# relays3.net
KiCad netlist of a schematic drawn in Altium Designer
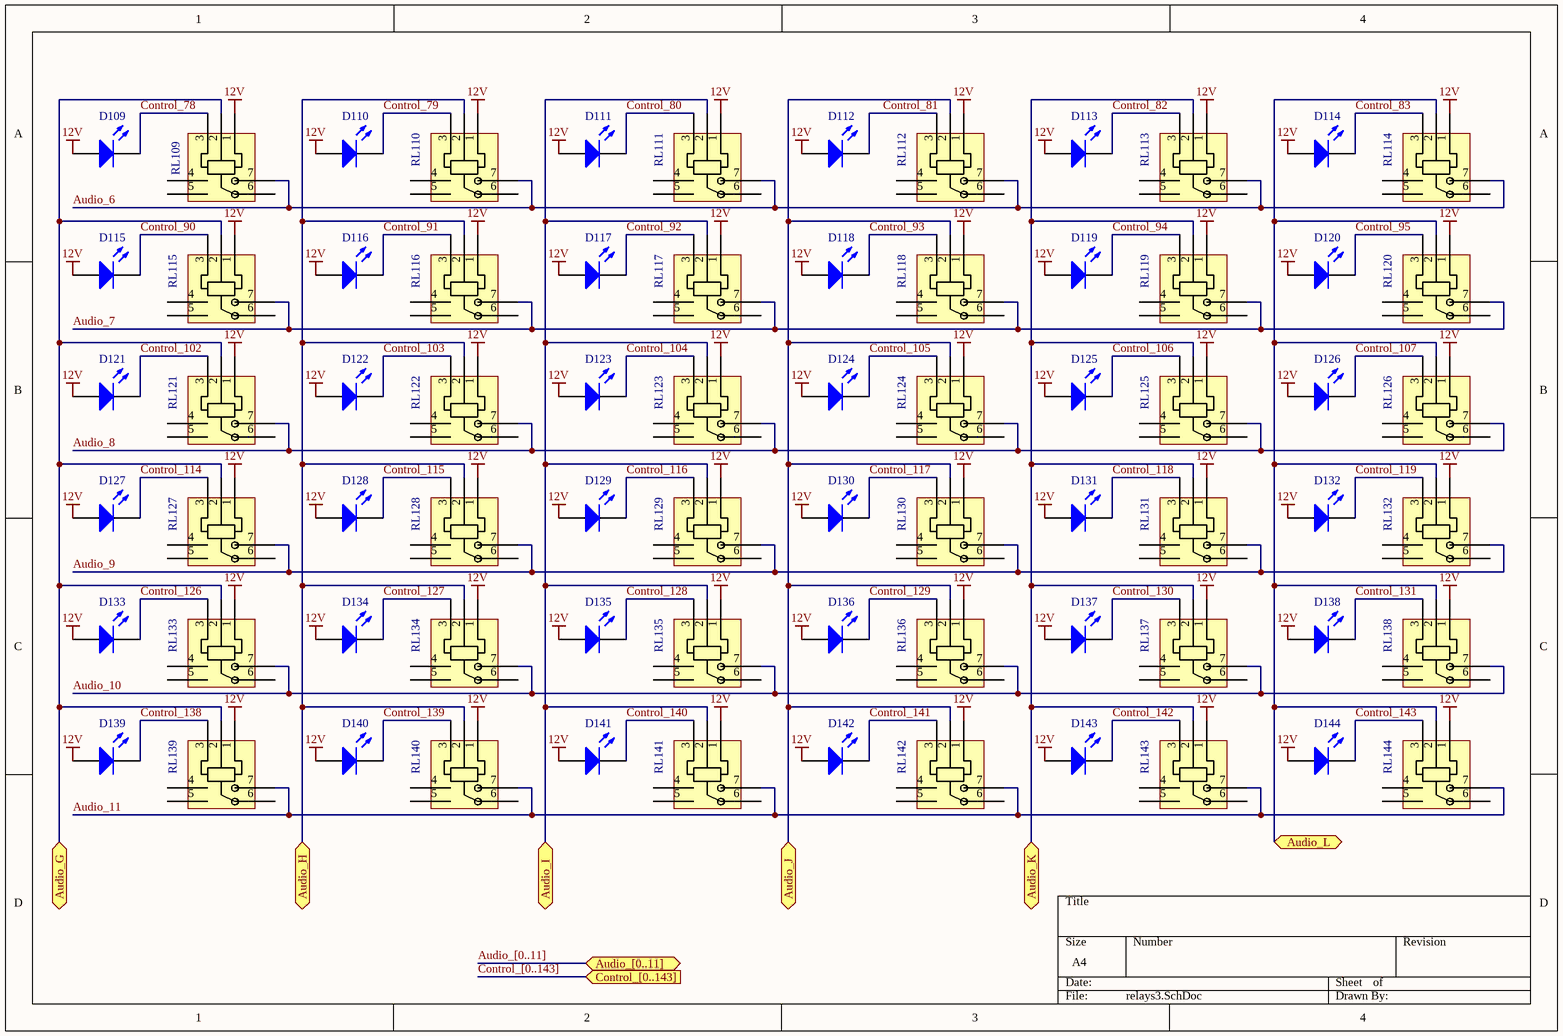
[diagram p0: relays3.SchDoc]

(export (version "E")
  (design (tool "Eeschema 10.0.6"))
  (components
    (comp (ref "D109")
      (value "LED0")
      (footprint "LED_round_5mm")
      (description "Typical INFRARED GaAs LED")
      (fields (field (name "PUBLISHER") "Altium Limited"))
      (libsource (lib "Miscellaneous Devices") (part "LED0"))
    )
    (comp (ref "D110")
      (value "LED0")
      (footprint "LED_round_5mm")
      (description "Typical INFRARED GaAs LED")
      (fields (field (name "PUBLISHER") "Altium Limited"))
      (libsource (lib "Miscellaneous Devices") (part "LED0"))
    )
    (comp (ref "D111")
      (value "LED0")
      (footprint "LED_round_5mm")
      (description "Typical INFRARED GaAs LED")
      (fields (field (name "PUBLISHER") "Altium Limited"))
      (libsource (lib "Miscellaneous Devices") (part "LED0"))
    )
    (comp (ref "D112")
      (value "LED0")
      (footprint "LED_round_5mm")
      (description "Typical INFRARED GaAs LED")
      (fields (field (name "PUBLISHER") "Altium Limited"))
      (libsource (lib "Miscellaneous Devices") (part "LED0"))
    )
    (comp (ref "D113")
      (value "LED0")
      (footprint "LED_round_5mm")
      (description "Typical INFRARED GaAs LED")
      (fields (field (name "PUBLISHER") "Altium Limited"))
      (libsource (lib "Miscellaneous Devices") (part "LED0"))
    )
    (comp (ref "D114")
      (value "LED0")
      (footprint "LED_round_5mm")
      (description "Typical INFRARED GaAs LED")
      (fields (field (name "PUBLISHER") "Altium Limited"))
      (libsource (lib "Miscellaneous Devices") (part "LED0"))
    )
    (comp (ref "D115")
      (value "LED0")
      (footprint "LED_round_5mm")
      (description "Typical INFRARED GaAs LED")
      (fields (field (name "PUBLISHER") "Altium Limited"))
      (libsource (lib "Miscellaneous Devices") (part "LED0"))
    )
    (comp (ref "D116")
      (value "LED0")
      (footprint "LED_round_5mm")
      (description "Typical INFRARED GaAs LED")
      (fields (field (name "PUBLISHER") "Altium Limited"))
      (libsource (lib "Miscellaneous Devices") (part "LED0"))
    )
    (comp (ref "D117")
      (value "LED0")
      (footprint "LED_round_5mm")
      (description "Typical INFRARED GaAs LED")
      (fields (field (name "PUBLISHER") "Altium Limited"))
      (libsource (lib "Miscellaneous Devices") (part "LED0"))
    )
    (comp (ref "D118")
      (value "LED0")
      (footprint "LED_round_5mm")
      (description "Typical INFRARED GaAs LED")
      (fields (field (name "PUBLISHER") "Altium Limited"))
      (libsource (lib "Miscellaneous Devices") (part "LED0"))
    )
    (comp (ref "D119")
      (value "LED0")
      (footprint "LED_round_5mm")
      (description "Typical INFRARED GaAs LED")
      (fields (field (name "PUBLISHER") "Altium Limited"))
      (libsource (lib "Miscellaneous Devices") (part "LED0"))
    )
    (comp (ref "D120")
      (value "LED0")
      (footprint "LED_round_5mm")
      (description "Typical INFRARED GaAs LED")
      (fields (field (name "PUBLISHER") "Altium Limited"))
      (libsource (lib "Miscellaneous Devices") (part "LED0"))
    )
    (comp (ref "D121")
      (value "LED0")
      (footprint "LED_round_5mm")
      (description "Typical INFRARED GaAs LED")
      (fields (field (name "PUBLISHER") "Altium Limited"))
      (libsource (lib "Miscellaneous Devices") (part "LED0"))
    )
    (comp (ref "D122")
      (value "LED0")
      (footprint "LED_round_5mm")
      (description "Typical INFRARED GaAs LED")
      (fields (field (name "PUBLISHER") "Altium Limited"))
      (libsource (lib "Miscellaneous Devices") (part "LED0"))
    )
    (comp (ref "D123")
      (value "LED0")
      (footprint "LED_round_5mm")
      (description "Typical INFRARED GaAs LED")
      (fields (field (name "PUBLISHER") "Altium Limited"))
      (libsource (lib "Miscellaneous Devices") (part "LED0"))
    )
    (comp (ref "D124")
      (value "LED0")
      (footprint "LED_round_5mm")
      (description "Typical INFRARED GaAs LED")
      (fields (field (name "PUBLISHER") "Altium Limited"))
      (libsource (lib "Miscellaneous Devices") (part "LED0"))
    )
    (comp (ref "D125")
      (value "LED0")
      (footprint "LED_round_5mm")
      (description "Typical INFRARED GaAs LED")
      (fields (field (name "PUBLISHER") "Altium Limited"))
      (libsource (lib "Miscellaneous Devices") (part "LED0"))
    )
    (comp (ref "D126")
      (value "LED0")
      (footprint "LED_round_5mm")
      (description "Typical INFRARED GaAs LED")
      (fields (field (name "PUBLISHER") "Altium Limited"))
      (libsource (lib "Miscellaneous Devices") (part "LED0"))
    )
    (comp (ref "D127")
      (value "LED0")
      (footprint "LED_round_5mm")
      (description "Typical INFRARED GaAs LED")
      (fields (field (name "PUBLISHER") "Altium Limited"))
      (libsource (lib "Miscellaneous Devices") (part "LED0"))
    )
    (comp (ref "D128")
      (value "LED0")
      (footprint "LED_round_5mm")
      (description "Typical INFRARED GaAs LED")
      (fields (field (name "PUBLISHER") "Altium Limited"))
      (libsource (lib "Miscellaneous Devices") (part "LED0"))
    )
    (comp (ref "D129")
      (value "LED0")
      (footprint "LED_round_5mm")
      (description "Typical INFRARED GaAs LED")
      (fields (field (name "PUBLISHER") "Altium Limited"))
      (libsource (lib "Miscellaneous Devices") (part "LED0"))
    )
    (comp (ref "D130")
      (value "LED0")
      (footprint "LED_round_5mm")
      (description "Typical INFRARED GaAs LED")
      (fields (field (name "PUBLISHER") "Altium Limited"))
      (libsource (lib "Miscellaneous Devices") (part "LED0"))
    )
    (comp (ref "D131")
      (value "LED0")
      (footprint "LED_round_5mm")
      (description "Typical INFRARED GaAs LED")
      (fields (field (name "PUBLISHER") "Altium Limited"))
      (libsource (lib "Miscellaneous Devices") (part "LED0"))
    )
    (comp (ref "D132")
      (value "LED0")
      (footprint "LED_round_5mm")
      (description "Typical INFRARED GaAs LED")
      (fields (field (name "PUBLISHER") "Altium Limited"))
      (libsource (lib "Miscellaneous Devices") (part "LED0"))
    )
    (comp (ref "D133")
      (value "LED0")
      (footprint "LED_round_5mm")
      (description "Typical INFRARED GaAs LED")
      (fields (field (name "PUBLISHER") "Altium Limited"))
      (libsource (lib "Miscellaneous Devices") (part "LED0"))
    )
    (comp (ref "D134")
      (value "LED0")
      (footprint "LED_round_5mm")
      (description "Typical INFRARED GaAs LED")
      (fields (field (name "PUBLISHER") "Altium Limited"))
      (libsource (lib "Miscellaneous Devices") (part "LED0"))
    )
    (comp (ref "D135")
      (value "LED0")
      (footprint "LED_round_5mm")
      (description "Typical INFRARED GaAs LED")
      (fields (field (name "PUBLISHER") "Altium Limited"))
      (libsource (lib "Miscellaneous Devices") (part "LED0"))
    )
    (comp (ref "D136")
      (value "LED0")
      (footprint "LED_round_5mm")
      (description "Typical INFRARED GaAs LED")
      (fields (field (name "PUBLISHER") "Altium Limited"))
      (libsource (lib "Miscellaneous Devices") (part "LED0"))
    )
    (comp (ref "D137")
      (value "LED0")
      (footprint "LED_round_5mm")
      (description "Typical INFRARED GaAs LED")
      (fields (field (name "PUBLISHER") "Altium Limited"))
      (libsource (lib "Miscellaneous Devices") (part "LED0"))
    )
    (comp (ref "D138")
      (value "LED0")
      (footprint "LED_round_5mm")
      (description "Typical INFRARED GaAs LED")
      (fields (field (name "PUBLISHER") "Altium Limited"))
      (libsource (lib "Miscellaneous Devices") (part "LED0"))
    )
    (comp (ref "D139")
      (value "LED0")
      (footprint "LED_round_5mm")
      (description "Typical INFRARED GaAs LED")
      (fields (field (name "PUBLISHER") "Altium Limited"))
      (libsource (lib "Miscellaneous Devices") (part "LED0"))
    )
    (comp (ref "D140")
      (value "LED0")
      (footprint "LED_round_5mm")
      (description "Typical INFRARED GaAs LED")
      (fields (field (name "PUBLISHER") "Altium Limited"))
      (libsource (lib "Miscellaneous Devices") (part "LED0"))
    )
    (comp (ref "D141")
      (value "LED0")
      (footprint "LED_round_5mm")
      (description "Typical INFRARED GaAs LED")
      (fields (field (name "PUBLISHER") "Altium Limited"))
      (libsource (lib "Miscellaneous Devices") (part "LED0"))
    )
    (comp (ref "D142")
      (value "LED0")
      (footprint "LED_round_5mm")
      (description "Typical INFRARED GaAs LED")
      (fields (field (name "PUBLISHER") "Altium Limited"))
      (libsource (lib "Miscellaneous Devices") (part "LED0"))
    )
    (comp (ref "D143")
      (value "LED0")
      (footprint "LED_round_5mm")
      (description "Typical INFRARED GaAs LED")
      (fields (field (name "PUBLISHER") "Altium Limited"))
      (libsource (lib "Miscellaneous Devices") (part "LED0"))
    )
    (comp (ref "D144")
      (value "LED0")
      (footprint "LED_round_5mm")
      (description "Typical INFRARED GaAs LED")
      (fields (field (name "PUBLISHER") "Altium Limited"))
      (libsource (lib "Miscellaneous Devices") (part "LED0"))
    )
    (comp (ref "RL109")
      (value "Relay")
      (footprint "Relay_FRA3")
      (description "Miniature power relay")
      (fields (field (name "PART NUMBER") "FRA3C-DC12"))
      (libsource (lib "tech-thing") (part "Relay_FRA3"))
    )
    (comp (ref "RL110")
      (value "Relay")
      (footprint "Relay_FRA3")
      (description "Miniature power relay")
      (fields (field (name "PART NUMBER") "FRA3C-DC12"))
      (libsource (lib "tech-thing") (part "Relay_FRA3"))
    )
    (comp (ref "RL111")
      (value "Relay")
      (footprint "Relay_FRA3")
      (description "Miniature power relay")
      (fields (field (name "PART NUMBER") "FRA3C-DC12"))
      (libsource (lib "tech-thing") (part "Relay_FRA3"))
    )
    (comp (ref "RL112")
      (value "Relay")
      (footprint "Relay_FRA3")
      (description "Miniature power relay")
      (fields (field (name "PART NUMBER") "FRA3C-DC12"))
      (libsource (lib "tech-thing") (part "Relay_FRA3"))
    )
    (comp (ref "RL113")
      (value "Relay")
      (footprint "Relay_FRA3")
      (description "Miniature power relay")
      (fields (field (name "PART NUMBER") "FRA3C-DC12"))
      (libsource (lib "tech-thing") (part "Relay_FRA3"))
    )
    (comp (ref "RL114")
      (value "Relay")
      (footprint "Relay_FRA3")
      (description "Miniature power relay")
      (fields (field (name "PART NUMBER") "FRA3C-DC12"))
      (libsource (lib "tech-thing") (part "Relay_FRA3"))
    )
    (comp (ref "RL115")
      (value "Relay")
      (footprint "Relay_FRA3")
      (description "Miniature power relay")
      (fields (field (name "PART NUMBER") "FRA3C-DC12"))
      (libsource (lib "tech-thing") (part "Relay_FRA3"))
    )
    (comp (ref "RL116")
      (value "Relay")
      (footprint "Relay_FRA3")
      (description "Miniature power relay")
      (fields (field (name "PART NUMBER") "FRA3C-DC12"))
      (libsource (lib "tech-thing") (part "Relay_FRA3"))
    )
    (comp (ref "RL117")
      (value "Relay")
      (footprint "Relay_FRA3")
      (description "Miniature power relay")
      (fields (field (name "PART NUMBER") "FRA3C-DC12"))
      (libsource (lib "tech-thing") (part "Relay_FRA3"))
    )
    (comp (ref "RL118")
      (value "Relay")
      (footprint "Relay_FRA3")
      (description "Miniature power relay")
      (fields (field (name "PART NUMBER") "FRA3C-DC12"))
      (libsource (lib "tech-thing") (part "Relay_FRA3"))
    )
    (comp (ref "RL119")
      (value "Relay")
      (footprint "Relay_FRA3")
      (description "Miniature power relay")
      (fields (field (name "PART NUMBER") "FRA3C-DC12"))
      (libsource (lib "tech-thing") (part "Relay_FRA3"))
    )
    (comp (ref "RL120")
      (value "Relay")
      (footprint "Relay_FRA3")
      (description "Miniature power relay")
      (fields (field (name "PART NUMBER") "FRA3C-DC12"))
      (libsource (lib "tech-thing") (part "Relay_FRA3"))
    )
    (comp (ref "RL121")
      (value "Relay")
      (footprint "Relay_FRA3")
      (description "Miniature power relay")
      (fields (field (name "PART NUMBER") "FRA3C-DC12"))
      (libsource (lib "tech-thing") (part "Relay_FRA3"))
    )
    (comp (ref "RL122")
      (value "Relay")
      (footprint "Relay_FRA3")
      (description "Miniature power relay")
      (fields (field (name "PART NUMBER") "FRA3C-DC12"))
      (libsource (lib "tech-thing") (part "Relay_FRA3"))
    )
    (comp (ref "RL123")
      (value "Relay")
      (footprint "Relay_FRA3")
      (description "Miniature power relay")
      (fields (field (name "PART NUMBER") "FRA3C-DC12"))
      (libsource (lib "tech-thing") (part "Relay_FRA3"))
    )
    (comp (ref "RL124")
      (value "Relay")
      (footprint "Relay_FRA3")
      (description "Miniature power relay")
      (fields (field (name "PART NUMBER") "FRA3C-DC12"))
      (libsource (lib "tech-thing") (part "Relay_FRA3"))
    )
    (comp (ref "RL125")
      (value "Relay")
      (footprint "Relay_FRA3")
      (description "Miniature power relay")
      (fields (field (name "PART NUMBER") "FRA3C-DC12"))
      (libsource (lib "tech-thing") (part "Relay_FRA3"))
    )
    (comp (ref "RL126")
      (value "Relay")
      (footprint "Relay_FRA3")
      (description "Miniature power relay")
      (fields (field (name "PART NUMBER") "FRA3C-DC12"))
      (libsource (lib "tech-thing") (part "Relay_FRA3"))
    )
    (comp (ref "RL127")
      (value "Relay")
      (footprint "Relay_FRA3")
      (description "Miniature power relay")
      (fields (field (name "PART NUMBER") "FRA3C-DC12"))
      (libsource (lib "tech-thing") (part "Relay_FRA3"))
    )
    (comp (ref "RL128")
      (value "Relay")
      (footprint "Relay_FRA3")
      (description "Miniature power relay")
      (fields (field (name "PART NUMBER") "FRA3C-DC12"))
      (libsource (lib "tech-thing") (part "Relay_FRA3"))
    )
    (comp (ref "RL129")
      (value "Relay")
      (footprint "Relay_FRA3")
      (description "Miniature power relay")
      (fields (field (name "PART NUMBER") "FRA3C-DC12"))
      (libsource (lib "tech-thing") (part "Relay_FRA3"))
    )
    (comp (ref "RL130")
      (value "Relay")
      (footprint "Relay_FRA3")
      (description "Miniature power relay")
      (fields (field (name "PART NUMBER") "FRA3C-DC12"))
      (libsource (lib "tech-thing") (part "Relay_FRA3"))
    )
    (comp (ref "RL131")
      (value "Relay")
      (footprint "Relay_FRA3")
      (description "Miniature power relay")
      (fields (field (name "PART NUMBER") "FRA3C-DC12"))
      (libsource (lib "tech-thing") (part "Relay_FRA3"))
    )
    (comp (ref "RL132")
      (value "Relay")
      (footprint "Relay_FRA3")
      (description "Miniature power relay")
      (fields (field (name "PART NUMBER") "FRA3C-DC12"))
      (libsource (lib "tech-thing") (part "Relay_FRA3"))
    )
    (comp (ref "RL133")
      (value "Relay")
      (footprint "Relay_FRA3")
      (description "Miniature power relay")
      (fields (field (name "PART NUMBER") "FRA3C-DC12"))
      (libsource (lib "tech-thing") (part "Relay_FRA3"))
    )
    (comp (ref "RL134")
      (value "Relay")
      (footprint "Relay_FRA3")
      (description "Miniature power relay")
      (fields (field (name "PART NUMBER") "FRA3C-DC12"))
      (libsource (lib "tech-thing") (part "Relay_FRA3"))
    )
    (comp (ref "RL135")
      (value "Relay")
      (footprint "Relay_FRA3")
      (description "Miniature power relay")
      (fields (field (name "PART NUMBER") "FRA3C-DC12"))
      (libsource (lib "tech-thing") (part "Relay_FRA3"))
    )
    (comp (ref "RL136")
      (value "Relay")
      (footprint "Relay_FRA3")
      (description "Miniature power relay")
      (fields (field (name "PART NUMBER") "FRA3C-DC12"))
      (libsource (lib "tech-thing") (part "Relay_FRA3"))
    )
    (comp (ref "RL137")
      (value "Relay")
      (footprint "Relay_FRA3")
      (description "Miniature power relay")
      (fields (field (name "PART NUMBER") "FRA3C-DC12"))
      (libsource (lib "tech-thing") (part "Relay_FRA3"))
    )
    (comp (ref "RL138")
      (value "Relay")
      (footprint "Relay_FRA3")
      (description "Miniature power relay")
      (fields (field (name "PART NUMBER") "FRA3C-DC12"))
      (libsource (lib "tech-thing") (part "Relay_FRA3"))
    )
    (comp (ref "RL139")
      (value "Relay")
      (footprint "Relay_FRA3")
      (description "Miniature power relay")
      (fields (field (name "PART NUMBER") "FRA3C-DC12"))
      (libsource (lib "tech-thing") (part "Relay_FRA3"))
    )
    (comp (ref "RL140")
      (value "Relay")
      (footprint "Relay_FRA3")
      (description "Miniature power relay")
      (fields (field (name "PART NUMBER") "FRA3C-DC12"))
      (libsource (lib "tech-thing") (part "Relay_FRA3"))
    )
    (comp (ref "RL141")
      (value "Relay")
      (footprint "Relay_FRA3")
      (description "Miniature power relay")
      (fields (field (name "PART NUMBER") "FRA3C-DC12"))
      (libsource (lib "tech-thing") (part "Relay_FRA3"))
    )
    (comp (ref "RL142")
      (value "Relay")
      (footprint "Relay_FRA3")
      (description "Miniature power relay")
      (fields (field (name "PART NUMBER") "FRA3C-DC12"))
      (libsource (lib "tech-thing") (part "Relay_FRA3"))
    )
    (comp (ref "RL143")
      (value "Relay")
      (footprint "Relay_FRA3")
      (description "Miniature power relay")
      (fields (field (name "PART NUMBER") "FRA3C-DC12"))
      (libsource (lib "tech-thing") (part "Relay_FRA3"))
    )
    (comp (ref "RL144")
      (value "Relay")
      (footprint "Relay_FRA3")
      (description "Miniature power relay")
      (fields (field (name "PART NUMBER") "FRA3C-DC12"))
      (libsource (lib "tech-thing") (part "Relay_FRA3"))
    )
  )
  (nets
    (net (code "115") (name "/Audio_6") (class "Default")
      (node (ref "RL109") (pin "7") (pintype "passive"))
      (node (ref "RL110") (pin "7") (pintype "passive"))
      (node (ref "RL111") (pin "7") (pintype "passive"))
      (node (ref "RL112") (pin "7") (pintype "passive"))
      (node (ref "RL113") (pin "7") (pintype "passive"))
      (node (ref "RL114") (pin "7") (pintype "passive"))
    )
    (net (code "116") (name "/Audio_7") (class "Default")
      (node (ref "RL115") (pin "7") (pintype "passive"))
      (node (ref "RL116") (pin "7") (pintype "passive"))
      (node (ref "RL117") (pin "7") (pintype "passive"))
      (node (ref "RL118") (pin "7") (pintype "passive"))
      (node (ref "RL119") (pin "7") (pintype "passive"))
      (node (ref "RL120") (pin "7") (pintype "passive"))
    )
    (net (code "117") (name "/Audio_8") (class "Default")
      (node (ref "RL121") (pin "7") (pintype "passive"))
      (node (ref "RL122") (pin "7") (pintype "passive"))
      (node (ref "RL123") (pin "7") (pintype "passive"))
      (node (ref "RL124") (pin "7") (pintype "passive"))
      (node (ref "RL125") (pin "7") (pintype "passive"))
      (node (ref "RL126") (pin "7") (pintype "passive"))
    )
    (net (code "118") (name "/Audio_9") (class "Default")
      (node (ref "RL127") (pin "7") (pintype "passive"))
      (node (ref "RL128") (pin "7") (pintype "passive"))
      (node (ref "RL129") (pin "7") (pintype "passive"))
      (node (ref "RL130") (pin "7") (pintype "passive"))
      (node (ref "RL131") (pin "7") (pintype "passive"))
      (node (ref "RL132") (pin "7") (pintype "passive"))
    )
    (net (code "119") (name "/Audio_10") (class "Default")
      (node (ref "RL133") (pin "7") (pintype "passive"))
      (node (ref "RL134") (pin "7") (pintype "passive"))
      (node (ref "RL135") (pin "7") (pintype "passive"))
      (node (ref "RL136") (pin "7") (pintype "passive"))
      (node (ref "RL137") (pin "7") (pintype "passive"))
      (node (ref "RL138") (pin "7") (pintype "passive"))
    )
    (net (code "120") (name "/Audio_11") (class "Default")
      (node (ref "RL139") (pin "7") (pintype "passive"))
      (node (ref "RL140") (pin "7") (pintype "passive"))
      (node (ref "RL141") (pin "7") (pintype "passive"))
      (node (ref "RL142") (pin "7") (pintype "passive"))
      (node (ref "RL143") (pin "7") (pintype "passive"))
      (node (ref "RL144") (pin "7") (pintype "passive"))
    )
    (net (code "121") (name "/Audio_G") (class "Default")
      (node (ref "RL109") (pin "2") (pintype "passive"))
      (node (ref "RL115") (pin "2") (pintype "passive"))
      (node (ref "RL121") (pin "2") (pintype "passive"))
      (node (ref "RL127") (pin "2") (pintype "passive"))
      (node (ref "RL133") (pin "2") (pintype "passive"))
      (node (ref "RL139") (pin "2") (pintype "passive"))
    )
    (net (code "122") (name "/Audio_H") (class "Default")
      (node (ref "RL110") (pin "2") (pintype "passive"))
      (node (ref "RL116") (pin "2") (pintype "passive"))
      (node (ref "RL122") (pin "2") (pintype "passive"))
      (node (ref "RL128") (pin "2") (pintype "passive"))
      (node (ref "RL134") (pin "2") (pintype "passive"))
      (node (ref "RL140") (pin "2") (pintype "passive"))
    )
    (net (code "123") (name "/Audio_I") (class "Default")
      (node (ref "RL111") (pin "2") (pintype "passive"))
      (node (ref "RL117") (pin "2") (pintype "passive"))
      (node (ref "RL123") (pin "2") (pintype "passive"))
      (node (ref "RL129") (pin "2") (pintype "passive"))
      (node (ref "RL135") (pin "2") (pintype "passive"))
      (node (ref "RL141") (pin "2") (pintype "passive"))
    )
    (net (code "124") (name "/Audio_J") (class "Default")
      (node (ref "RL112") (pin "2") (pintype "passive"))
      (node (ref "RL118") (pin "2") (pintype "passive"))
      (node (ref "RL124") (pin "2") (pintype "passive"))
      (node (ref "RL130") (pin "2") (pintype "passive"))
      (node (ref "RL136") (pin "2") (pintype "passive"))
      (node (ref "RL142") (pin "2") (pintype "passive"))
    )
    (net (code "125") (name "/Audio_K") (class "Default")
      (node (ref "RL113") (pin "2") (pintype "passive"))
      (node (ref "RL119") (pin "2") (pintype "passive"))
      (node (ref "RL125") (pin "2") (pintype "passive"))
      (node (ref "RL131") (pin "2") (pintype "passive"))
      (node (ref "RL137") (pin "2") (pintype "passive"))
      (node (ref "RL143") (pin "2") (pintype "passive"))
    )
    (net (code "126") (name "/Audio_L") (class "Default")
      (node (ref "RL114") (pin "2") (pintype "passive"))
      (node (ref "RL120") (pin "2") (pintype "passive"))
      (node (ref "RL126") (pin "2") (pintype "passive"))
      (node (ref "RL132") (pin "2") (pintype "passive"))
      (node (ref "RL138") (pin "2") (pintype "passive"))
      (node (ref "RL144") (pin "2") (pintype "passive"))
    )
    (net (code "128") (name "/Control_78") (class "Default")
      (node (ref "D109") (pin "2") (pinfunction "K_2") (pintype "passive"))
      (node (ref "RL109") (pin "3") (pintype "passive"))
    )
    (net (code "129") (name "/Control_79") (class "Default")
      (node (ref "D110") (pin "2") (pinfunction "K_2") (pintype "passive"))
      (node (ref "RL110") (pin "3") (pintype "passive"))
    )
    (net (code "130") (name "/Control_80") (class "Default")
      (node (ref "D111") (pin "2") (pinfunction "K_2") (pintype "passive"))
      (node (ref "RL111") (pin "3") (pintype "passive"))
    )
    (net (code "131") (name "/Control_81") (class "Default")
      (node (ref "D112") (pin "2") (pinfunction "K_2") (pintype "passive"))
      (node (ref "RL112") (pin "3") (pintype "passive"))
    )
    (net (code "132") (name "/Control_82") (class "Default")
      (node (ref "D113") (pin "2") (pinfunction "K_2") (pintype "passive"))
      (node (ref "RL113") (pin "3") (pintype "passive"))
    )
    (net (code "133") (name "/Control_83") (class "Default")
      (node (ref "D114") (pin "2") (pinfunction "K_2") (pintype "passive"))
      (node (ref "RL114") (pin "3") (pintype "passive"))
    )
    (net (code "134") (name "/Control_90") (class "Default")
      (node (ref "D115") (pin "2") (pinfunction "K_2") (pintype "passive"))
      (node (ref "RL115") (pin "3") (pintype "passive"))
    )
    (net (code "135") (name "/Control_91") (class "Default")
      (node (ref "D116") (pin "2") (pinfunction "K_2") (pintype "passive"))
      (node (ref "RL116") (pin "3") (pintype "passive"))
    )
    (net (code "136") (name "/Control_92") (class "Default")
      (node (ref "D117") (pin "2") (pinfunction "K_2") (pintype "passive"))
      (node (ref "RL117") (pin "3") (pintype "passive"))
    )
    (net (code "137") (name "/Control_93") (class "Default")
      (node (ref "D118") (pin "2") (pinfunction "K_2") (pintype "passive"))
      (node (ref "RL118") (pin "3") (pintype "passive"))
    )
    (net (code "138") (name "/Control_94") (class "Default")
      (node (ref "D119") (pin "2") (pinfunction "K_2") (pintype "passive"))
      (node (ref "RL119") (pin "3") (pintype "passive"))
    )
    (net (code "139") (name "/Control_95") (class "Default")
      (node (ref "D120") (pin "2") (pinfunction "K_2") (pintype "passive"))
      (node (ref "RL120") (pin "3") (pintype "passive"))
    )
    (net (code "140") (name "/Control_102") (class "Default")
      (node (ref "D121") (pin "2") (pinfunction "K_2") (pintype "passive"))
      (node (ref "RL121") (pin "3") (pintype "passive"))
    )
    (net (code "141") (name "/Control_103") (class "Default")
      (node (ref "D122") (pin "2") (pinfunction "K_2") (pintype "passive"))
      (node (ref "RL122") (pin "3") (pintype "passive"))
    )
    (net (code "142") (name "/Control_104") (class "Default")
      (node (ref "D123") (pin "2") (pinfunction "K_2") (pintype "passive"))
      (node (ref "RL123") (pin "3") (pintype "passive"))
    )
    (net (code "143") (name "/Control_105") (class "Default")
      (node (ref "D124") (pin "2") (pinfunction "K_2") (pintype "passive"))
      (node (ref "RL124") (pin "3") (pintype "passive"))
    )
    (net (code "144") (name "/Control_106") (class "Default")
      (node (ref "D125") (pin "2") (pinfunction "K_2") (pintype "passive"))
      (node (ref "RL125") (pin "3") (pintype "passive"))
    )
    (net (code "145") (name "/Control_107") (class "Default")
      (node (ref "D126") (pin "2") (pinfunction "K_2") (pintype "passive"))
      (node (ref "RL126") (pin "3") (pintype "passive"))
    )
    (net (code "146") (name "/Control_114") (class "Default")
      (node (ref "D127") (pin "2") (pinfunction "K_2") (pintype "passive"))
      (node (ref "RL127") (pin "3") (pintype "passive"))
    )
    (net (code "147") (name "/Control_115") (class "Default")
      (node (ref "D128") (pin "2") (pinfunction "K_2") (pintype "passive"))
      (node (ref "RL128") (pin "3") (pintype "passive"))
    )
    (net (code "148") (name "/Control_116") (class "Default")
      (node (ref "D129") (pin "2") (pinfunction "K_2") (pintype "passive"))
      (node (ref "RL129") (pin "3") (pintype "passive"))
    )
    (net (code "149") (name "/Control_117") (class "Default")
      (node (ref "D130") (pin "2") (pinfunction "K_2") (pintype "passive"))
      (node (ref "RL130") (pin "3") (pintype "passive"))
    )
    (net (code "150") (name "/Control_118") (class "Default")
      (node (ref "D131") (pin "2") (pinfunction "K_2") (pintype "passive"))
      (node (ref "RL131") (pin "3") (pintype "passive"))
    )
    (net (code "151") (name "/Control_119") (class "Default")
      (node (ref "D132") (pin "2") (pinfunction "K_2") (pintype "passive"))
      (node (ref "RL132") (pin "3") (pintype "passive"))
    )
    (net (code "152") (name "/Control_126") (class "Default")
      (node (ref "D133") (pin "2") (pinfunction "K_2") (pintype "passive"))
      (node (ref "RL133") (pin "3") (pintype "passive"))
    )
    (net (code "153") (name "/Control_127") (class "Default")
      (node (ref "D134") (pin "2") (pinfunction "K_2") (pintype "passive"))
      (node (ref "RL134") (pin "3") (pintype "passive"))
    )
    (net (code "154") (name "/Control_128") (class "Default")
      (node (ref "D135") (pin "2") (pinfunction "K_2") (pintype "passive"))
      (node (ref "RL135") (pin "3") (pintype "passive"))
    )
    (net (code "155") (name "/Control_129") (class "Default")
      (node (ref "D136") (pin "2") (pinfunction "K_2") (pintype "passive"))
      (node (ref "RL136") (pin "3") (pintype "passive"))
    )
    (net (code "156") (name "/Control_130") (class "Default")
      (node (ref "D137") (pin "2") (pinfunction "K_2") (pintype "passive"))
      (node (ref "RL137") (pin "3") (pintype "passive"))
    )
    (net (code "157") (name "/Control_131") (class "Default")
      (node (ref "D138") (pin "2") (pinfunction "K_2") (pintype "passive"))
      (node (ref "RL138") (pin "3") (pintype "passive"))
    )
    (net (code "158") (name "/Control_138") (class "Default")
      (node (ref "D139") (pin "2") (pinfunction "K_2") (pintype "passive"))
      (node (ref "RL139") (pin "3") (pintype "passive"))
    )
    (net (code "159") (name "/Control_139") (class "Default")
      (node (ref "D140") (pin "2") (pinfunction "K_2") (pintype "passive"))
      (node (ref "RL140") (pin "3") (pintype "passive"))
    )
    (net (code "160") (name "/Control_140") (class "Default")
      (node (ref "D141") (pin "2") (pinfunction "K_2") (pintype "passive"))
      (node (ref "RL141") (pin "3") (pintype "passive"))
    )
    (net (code "161") (name "/Control_141") (class "Default")
      (node (ref "D142") (pin "2") (pinfunction "K_2") (pintype "passive"))
      (node (ref "RL142") (pin "3") (pintype "passive"))
    )
    (net (code "162") (name "/Control_142") (class "Default")
      (node (ref "D143") (pin "2") (pinfunction "K_2") (pintype "passive"))
      (node (ref "RL143") (pin "3") (pintype "passive"))
    )
    (net (code "163") (name "/Control_143") (class "Default")
      (node (ref "D144") (pin "2") (pinfunction "K_2") (pintype "passive"))
      (node (ref "RL144") (pin "3") (pintype "passive"))
    )
    (net (code "165") (name "12V") (class "Default")
      (node (ref "D109") (pin "1") (pinfunction "A_1") (pintype "passive"))
      (node (ref "D110") (pin "1") (pinfunction "A_1") (pintype "passive"))
      (node (ref "D111") (pin "1") (pinfunction "A_1") (pintype "passive"))
      (node (ref "D112") (pin "1") (pinfunction "A_1") (pintype "passive"))
      (node (ref "D113") (pin "1") (pinfunction "A_1") (pintype "passive"))
      (node (ref "D114") (pin "1") (pinfunction "A_1") (pintype "passive"))
      (node (ref "D115") (pin "1") (pinfunction "A_1") (pintype "passive"))
      (node (ref "D116") (pin "1") (pinfunction "A_1") (pintype "passive"))
      (node (ref "D117") (pin "1") (pinfunction "A_1") (pintype "passive"))
      (node (ref "D118") (pin "1") (pinfunction "A_1") (pintype "passive"))
      (node (ref "D119") (pin "1") (pinfunction "A_1") (pintype "passive"))
      (node (ref "D120") (pin "1") (pinfunction "A_1") (pintype "passive"))
      (node (ref "D121") (pin "1") (pinfunction "A_1") (pintype "passive"))
      (node (ref "D122") (pin "1") (pinfunction "A_1") (pintype "passive"))
      (node (ref "D123") (pin "1") (pinfunction "A_1") (pintype "passive"))
      (node (ref "D124") (pin "1") (pinfunction "A_1") (pintype "passive"))
      (node (ref "D125") (pin "1") (pinfunction "A_1") (pintype "passive"))
      (node (ref "D126") (pin "1") (pinfunction "A_1") (pintype "passive"))
      (node (ref "D127") (pin "1") (pinfunction "A_1") (pintype "passive"))
      (node (ref "D128") (pin "1") (pinfunction "A_1") (pintype "passive"))
      (node (ref "D129") (pin "1") (pinfunction "A_1") (pintype "passive"))
      (node (ref "D130") (pin "1") (pinfunction "A_1") (pintype "passive"))
      (node (ref "D131") (pin "1") (pinfunction "A_1") (pintype "passive"))
      (node (ref "D132") (pin "1") (pinfunction "A_1") (pintype "passive"))
      (node (ref "D133") (pin "1") (pinfunction "A_1") (pintype "passive"))
      (node (ref "D134") (pin "1") (pinfunction "A_1") (pintype "passive"))
      (node (ref "D135") (pin "1") (pinfunction "A_1") (pintype "passive"))
      (node (ref "D136") (pin "1") (pinfunction "A_1") (pintype "passive"))
      (node (ref "D137") (pin "1") (pinfunction "A_1") (pintype "passive"))
      (node (ref "D138") (pin "1") (pinfunction "A_1") (pintype "passive"))
      (node (ref "D139") (pin "1") (pinfunction "A_1") (pintype "passive"))
      (node (ref "D140") (pin "1") (pinfunction "A_1") (pintype "passive"))
      (node (ref "D141") (pin "1") (pinfunction "A_1") (pintype "passive"))
      (node (ref "D142") (pin "1") (pinfunction "A_1") (pintype "passive"))
      (node (ref "D143") (pin "1") (pinfunction "A_1") (pintype "passive"))
      (node (ref "D144") (pin "1") (pinfunction "A_1") (pintype "passive"))
      (node (ref "RL109") (pin "1") (pintype "passive"))
      (node (ref "RL110") (pin "1") (pintype "passive"))
      (node (ref "RL111") (pin "1") (pintype "passive"))
      (node (ref "RL112") (pin "1") (pintype "passive"))
      (node (ref "RL113") (pin "1") (pintype "passive"))
      (node (ref "RL114") (pin "1") (pintype "passive"))
      (node (ref "RL115") (pin "1") (pintype "passive"))
      (node (ref "RL116") (pin "1") (pintype "passive"))
      (node (ref "RL117") (pin "1") (pintype "passive"))
      (node (ref "RL118") (pin "1") (pintype "passive"))
      (node (ref "RL119") (pin "1") (pintype "passive"))
      (node (ref "RL120") (pin "1") (pintype "passive"))
      (node (ref "RL121") (pin "1") (pintype "passive"))
      (node (ref "RL122") (pin "1") (pintype "passive"))
      (node (ref "RL123") (pin "1") (pintype "passive"))
      (node (ref "RL124") (pin "1") (pintype "passive"))
      (node (ref "RL125") (pin "1") (pintype "passive"))
      (node (ref "RL126") (pin "1") (pintype "passive"))
      (node (ref "RL127") (pin "1") (pintype "passive"))
      (node (ref "RL128") (pin "1") (pintype "passive"))
      (node (ref "RL129") (pin "1") (pintype "passive"))
      (node (ref "RL130") (pin "1") (pintype "passive"))
      (node (ref "RL131") (pin "1") (pintype "passive"))
      (node (ref "RL132") (pin "1") (pintype "passive"))
      (node (ref "RL133") (pin "1") (pintype "passive"))
      (node (ref "RL134") (pin "1") (pintype "passive"))
      (node (ref "RL135") (pin "1") (pintype "passive"))
      (node (ref "RL136") (pin "1") (pintype "passive"))
      (node (ref "RL137") (pin "1") (pintype "passive"))
      (node (ref "RL138") (pin "1") (pintype "passive"))
      (node (ref "RL139") (pin "1") (pintype "passive"))
      (node (ref "RL140") (pin "1") (pintype "passive"))
      (node (ref "RL141") (pin "1") (pintype "passive"))
      (node (ref "RL142") (pin "1") (pintype "passive"))
      (node (ref "RL143") (pin "1") (pintype "passive"))
      (node (ref "RL144") (pin "1") (pintype "passive"))
    )
    (net (code "166") (name "unconnected-(RL109-Pad4)") (class "Default")
      (node (ref "RL109") (pin "4") (pintype "passive"))
    )
    (net (code "167") (name "unconnected-(RL109-Pad5)") (class "Default")
      (node (ref "RL109") (pin "5") (pintype "passive"))
    )
    (net (code "168") (name "unconnected-(RL109-Pad6)") (class "Default")
      (node (ref "RL109") (pin "6") (pintype "passive"))
    )
    (net (code "169") (name "unconnected-(RL110-Pad4)") (class "Default")
      (node (ref "RL110") (pin "4") (pintype "passive"))
    )
    (net (code "170") (name "unconnected-(RL110-Pad5)") (class "Default")
      (node (ref "RL110") (pin "5") (pintype "passive"))
    )
    (net (code "171") (name "unconnected-(RL110-Pad6)") (class "Default")
      (node (ref "RL110") (pin "6") (pintype "passive"))
    )
    (net (code "172") (name "unconnected-(RL111-Pad4)") (class "Default")
      (node (ref "RL111") (pin "4") (pintype "passive"))
    )
    (net (code "173") (name "unconnected-(RL111-Pad5)") (class "Default")
      (node (ref "RL111") (pin "5") (pintype "passive"))
    )
    (net (code "174") (name "unconnected-(RL111-Pad6)") (class "Default")
      (node (ref "RL111") (pin "6") (pintype "passive"))
    )
    (net (code "175") (name "unconnected-(RL112-Pad4)") (class "Default")
      (node (ref "RL112") (pin "4") (pintype "passive"))
    )
    (net (code "176") (name "unconnected-(RL112-Pad5)") (class "Default")
      (node (ref "RL112") (pin "5") (pintype "passive"))
    )
    (net (code "177") (name "unconnected-(RL112-Pad6)") (class "Default")
      (node (ref "RL112") (pin "6") (pintype "passive"))
    )
    (net (code "178") (name "unconnected-(RL113-Pad4)") (class "Default")
      (node (ref "RL113") (pin "4") (pintype "passive"))
    )
    (net (code "179") (name "unconnected-(RL113-Pad5)") (class "Default")
      (node (ref "RL113") (pin "5") (pintype "passive"))
    )
    (net (code "180") (name "unconnected-(RL113-Pad6)") (class "Default")
      (node (ref "RL113") (pin "6") (pintype "passive"))
    )
    (net (code "181") (name "unconnected-(RL114-Pad4)") (class "Default")
      (node (ref "RL114") (pin "4") (pintype "passive"))
    )
    (net (code "182") (name "unconnected-(RL114-Pad5)") (class "Default")
      (node (ref "RL114") (pin "5") (pintype "passive"))
    )
    (net (code "183") (name "unconnected-(RL114-Pad6)") (class "Default")
      (node (ref "RL114") (pin "6") (pintype "passive"))
    )
    (net (code "184") (name "unconnected-(RL115-Pad4)") (class "Default")
      (node (ref "RL115") (pin "4") (pintype "passive"))
    )
    (net (code "185") (name "unconnected-(RL115-Pad5)") (class "Default")
      (node (ref "RL115") (pin "5") (pintype "passive"))
    )
    (net (code "186") (name "unconnected-(RL115-Pad6)") (class "Default")
      (node (ref "RL115") (pin "6") (pintype "passive"))
    )
    (net (code "187") (name "unconnected-(RL116-Pad4)") (class "Default")
      (node (ref "RL116") (pin "4") (pintype "passive"))
    )
    (net (code "188") (name "unconnected-(RL116-Pad5)") (class "Default")
      (node (ref "RL116") (pin "5") (pintype "passive"))
    )
    (net (code "189") (name "unconnected-(RL116-Pad6)") (class "Default")
      (node (ref "RL116") (pin "6") (pintype "passive"))
    )
    (net (code "190") (name "unconnected-(RL117-Pad4)") (class "Default")
      (node (ref "RL117") (pin "4") (pintype "passive"))
    )
    (net (code "191") (name "unconnected-(RL117-Pad5)") (class "Default")
      (node (ref "RL117") (pin "5") (pintype "passive"))
    )
    (net (code "192") (name "unconnected-(RL117-Pad6)") (class "Default")
      (node (ref "RL117") (pin "6") (pintype "passive"))
    )
    (net (code "193") (name "unconnected-(RL118-Pad4)") (class "Default")
      (node (ref "RL118") (pin "4") (pintype "passive"))
    )
    (net (code "194") (name "unconnected-(RL118-Pad5)") (class "Default")
      (node (ref "RL118") (pin "5") (pintype "passive"))
    )
    (net (code "195") (name "unconnected-(RL118-Pad6)") (class "Default")
      (node (ref "RL118") (pin "6") (pintype "passive"))
    )
    (net (code "196") (name "unconnected-(RL119-Pad4)") (class "Default")
      (node (ref "RL119") (pin "4") (pintype "passive"))
    )
    (net (code "197") (name "unconnected-(RL119-Pad5)") (class "Default")
      (node (ref "RL119") (pin "5") (pintype "passive"))
    )
    (net (code "198") (name "unconnected-(RL119-Pad6)") (class "Default")
      (node (ref "RL119") (pin "6") (pintype "passive"))
    )
    (net (code "199") (name "unconnected-(RL120-Pad4)") (class "Default")
      (node (ref "RL120") (pin "4") (pintype "passive"))
    )
    (net (code "200") (name "unconnected-(RL120-Pad5)") (class "Default")
      (node (ref "RL120") (pin "5") (pintype "passive"))
    )
    (net (code "201") (name "unconnected-(RL120-Pad6)") (class "Default")
      (node (ref "RL120") (pin "6") (pintype "passive"))
    )
    (net (code "202") (name "unconnected-(RL121-Pad4)") (class "Default")
      (node (ref "RL121") (pin "4") (pintype "passive"))
    )
    (net (code "203") (name "unconnected-(RL121-Pad5)") (class "Default")
      (node (ref "RL121") (pin "5") (pintype "passive"))
    )
    (net (code "204") (name "unconnected-(RL121-Pad6)") (class "Default")
      (node (ref "RL121") (pin "6") (pintype "passive"))
    )
    (net (code "205") (name "unconnected-(RL122-Pad4)") (class "Default")
      (node (ref "RL122") (pin "4") (pintype "passive"))
    )
    (net (code "206") (name "unconnected-(RL122-Pad5)") (class "Default")
      (node (ref "RL122") (pin "5") (pintype "passive"))
    )
    (net (code "207") (name "unconnected-(RL122-Pad6)") (class "Default")
      (node (ref "RL122") (pin "6") (pintype "passive"))
    )
    (net (code "208") (name "unconnected-(RL123-Pad4)") (class "Default")
      (node (ref "RL123") (pin "4") (pintype "passive"))
    )
    (net (code "209") (name "unconnected-(RL123-Pad5)") (class "Default")
      (node (ref "RL123") (pin "5") (pintype "passive"))
    )
    (net (code "210") (name "unconnected-(RL123-Pad6)") (class "Default")
      (node (ref "RL123") (pin "6") (pintype "passive"))
    )
    (net (code "211") (name "unconnected-(RL124-Pad4)") (class "Default")
      (node (ref "RL124") (pin "4") (pintype "passive"))
    )
    (net (code "212") (name "unconnected-(RL124-Pad5)") (class "Default")
      (node (ref "RL124") (pin "5") (pintype "passive"))
    )
    (net (code "213") (name "unconnected-(RL124-Pad6)") (class "Default")
      (node (ref "RL124") (pin "6") (pintype "passive"))
    )
    (net (code "214") (name "unconnected-(RL125-Pad4)") (class "Default")
      (node (ref "RL125") (pin "4") (pintype "passive"))
    )
    (net (code "215") (name "unconnected-(RL125-Pad5)") (class "Default")
      (node (ref "RL125") (pin "5") (pintype "passive"))
    )
    (net (code "216") (name "unconnected-(RL125-Pad6)") (class "Default")
      (node (ref "RL125") (pin "6") (pintype "passive"))
    )
    (net (code "217") (name "unconnected-(RL126-Pad4)") (class "Default")
      (node (ref "RL126") (pin "4") (pintype "passive"))
    )
    (net (code "218") (name "unconnected-(RL126-Pad5)") (class "Default")
      (node (ref "RL126") (pin "5") (pintype "passive"))
    )
    (net (code "219") (name "unconnected-(RL126-Pad6)") (class "Default")
      (node (ref "RL126") (pin "6") (pintype "passive"))
    )
    (net (code "220") (name "unconnected-(RL127-Pad4)") (class "Default")
      (node (ref "RL127") (pin "4") (pintype "passive"))
    )
    (net (code "221") (name "unconnected-(RL127-Pad5)") (class "Default")
      (node (ref "RL127") (pin "5") (pintype "passive"))
    )
    (net (code "222") (name "unconnected-(RL127-Pad6)") (class "Default")
      (node (ref "RL127") (pin "6") (pintype "passive"))
    )
    (net (code "223") (name "unconnected-(RL128-Pad4)") (class "Default")
      (node (ref "RL128") (pin "4") (pintype "passive"))
    )
    (net (code "224") (name "unconnected-(RL128-Pad5)") (class "Default")
      (node (ref "RL128") (pin "5") (pintype "passive"))
    )
    (net (code "225") (name "unconnected-(RL128-Pad6)") (class "Default")
      (node (ref "RL128") (pin "6") (pintype "passive"))
    )
    (net (code "226") (name "unconnected-(RL129-Pad4)") (class "Default")
      (node (ref "RL129") (pin "4") (pintype "passive"))
    )
    (net (code "227") (name "unconnected-(RL129-Pad5)") (class "Default")
      (node (ref "RL129") (pin "5") (pintype "passive"))
    )
    (net (code "228") (name "unconnected-(RL129-Pad6)") (class "Default")
      (node (ref "RL129") (pin "6") (pintype "passive"))
    )
    (net (code "229") (name "unconnected-(RL130-Pad4)") (class "Default")
      (node (ref "RL130") (pin "4") (pintype "passive"))
    )
    (net (code "230") (name "unconnected-(RL130-Pad5)") (class "Default")
      (node (ref "RL130") (pin "5") (pintype "passive"))
    )
    (net (code "231") (name "unconnected-(RL130-Pad6)") (class "Default")
      (node (ref "RL130") (pin "6") (pintype "passive"))
    )
    (net (code "232") (name "unconnected-(RL131-Pad4)") (class "Default")
      (node (ref "RL131") (pin "4") (pintype "passive"))
    )
    (net (code "233") (name "unconnected-(RL131-Pad5)") (class "Default")
      (node (ref "RL131") (pin "5") (pintype "passive"))
    )
    (net (code "234") (name "unconnected-(RL131-Pad6)") (class "Default")
      (node (ref "RL131") (pin "6") (pintype "passive"))
    )
    (net (code "235") (name "unconnected-(RL132-Pad4)") (class "Default")
      (node (ref "RL132") (pin "4") (pintype "passive"))
    )
    (net (code "236") (name "unconnected-(RL132-Pad5)") (class "Default")
      (node (ref "RL132") (pin "5") (pintype "passive"))
    )
    (net (code "237") (name "unconnected-(RL132-Pad6)") (class "Default")
      (node (ref "RL132") (pin "6") (pintype "passive"))
    )
    (net (code "238") (name "unconnected-(RL133-Pad4)") (class "Default")
      (node (ref "RL133") (pin "4") (pintype "passive"))
    )
    (net (code "239") (name "unconnected-(RL133-Pad5)") (class "Default")
      (node (ref "RL133") (pin "5") (pintype "passive"))
    )
    (net (code "240") (name "unconnected-(RL133-Pad6)") (class "Default")
      (node (ref "RL133") (pin "6") (pintype "passive"))
    )
    (net (code "241") (name "unconnected-(RL134-Pad4)") (class "Default")
      (node (ref "RL134") (pin "4") (pintype "passive"))
    )
    (net (code "242") (name "unconnected-(RL134-Pad5)") (class "Default")
      (node (ref "RL134") (pin "5") (pintype "passive"))
    )
    (net (code "243") (name "unconnected-(RL134-Pad6)") (class "Default")
      (node (ref "RL134") (pin "6") (pintype "passive"))
    )
    (net (code "244") (name "unconnected-(RL135-Pad4)") (class "Default")
      (node (ref "RL135") (pin "4") (pintype "passive"))
    )
    (net (code "245") (name "unconnected-(RL135-Pad5)") (class "Default")
      (node (ref "RL135") (pin "5") (pintype "passive"))
    )
    (net (code "246") (name "unconnected-(RL135-Pad6)") (class "Default")
      (node (ref "RL135") (pin "6") (pintype "passive"))
    )
    (net (code "247") (name "unconnected-(RL136-Pad4)") (class "Default")
      (node (ref "RL136") (pin "4") (pintype "passive"))
    )
    (net (code "248") (name "unconnected-(RL136-Pad5)") (class "Default")
      (node (ref "RL136") (pin "5") (pintype "passive"))
    )
    (net (code "249") (name "unconnected-(RL136-Pad6)") (class "Default")
      (node (ref "RL136") (pin "6") (pintype "passive"))
    )
    (net (code "250") (name "unconnected-(RL137-Pad4)") (class "Default")
      (node (ref "RL137") (pin "4") (pintype "passive"))
    )
    (net (code "251") (name "unconnected-(RL137-Pad5)") (class "Default")
      (node (ref "RL137") (pin "5") (pintype "passive"))
    )
    (net (code "252") (name "unconnected-(RL137-Pad6)") (class "Default")
      (node (ref "RL137") (pin "6") (pintype "passive"))
    )
    (net (code "253") (name "unconnected-(RL138-Pad4)") (class "Default")
      (node (ref "RL138") (pin "4") (pintype "passive"))
    )
    (net (code "254") (name "unconnected-(RL138-Pad5)") (class "Default")
      (node (ref "RL138") (pin "5") (pintype "passive"))
    )
    (net (code "255") (name "unconnected-(RL138-Pad6)") (class "Default")
      (node (ref "RL138") (pin "6") (pintype "passive"))
    )
    (net (code "256") (name "unconnected-(RL139-Pad4)") (class "Default")
      (node (ref "RL139") (pin "4") (pintype "passive"))
    )
    (net (code "257") (name "unconnected-(RL139-Pad5)") (class "Default")
      (node (ref "RL139") (pin "5") (pintype "passive"))
    )
    (net (code "258") (name "unconnected-(RL139-Pad6)") (class "Default")
      (node (ref "RL139") (pin "6") (pintype "passive"))
    )
    (net (code "259") (name "unconnected-(RL140-Pad4)") (class "Default")
      (node (ref "RL140") (pin "4") (pintype "passive"))
    )
    (net (code "260") (name "unconnected-(RL140-Pad5)") (class "Default")
      (node (ref "RL140") (pin "5") (pintype "passive"))
    )
    (net (code "261") (name "unconnected-(RL140-Pad6)") (class "Default")
      (node (ref "RL140") (pin "6") (pintype "passive"))
    )
    (net (code "262") (name "unconnected-(RL141-Pad4)") (class "Default")
      (node (ref "RL141") (pin "4") (pintype "passive"))
    )
    (net (code "263") (name "unconnected-(RL141-Pad5)") (class "Default")
      (node (ref "RL141") (pin "5") (pintype "passive"))
    )
    (net (code "264") (name "unconnected-(RL141-Pad6)") (class "Default")
      (node (ref "RL141") (pin "6") (pintype "passive"))
    )
    (net (code "265") (name "unconnected-(RL142-Pad4)") (class "Default")
      (node (ref "RL142") (pin "4") (pintype "passive"))
    )
    (net (code "266") (name "unconnected-(RL142-Pad5)") (class "Default")
      (node (ref "RL142") (pin "5") (pintype "passive"))
    )
    (net (code "267") (name "unconnected-(RL142-Pad6)") (class "Default")
      (node (ref "RL142") (pin "6") (pintype "passive"))
    )
    (net (code "268") (name "unconnected-(RL143-Pad4)") (class "Default")
      (node (ref "RL143") (pin "4") (pintype "passive"))
    )
    (net (code "269") (name "unconnected-(RL143-Pad5)") (class "Default")
      (node (ref "RL143") (pin "5") (pintype "passive"))
    )
    (net (code "270") (name "unconnected-(RL143-Pad6)") (class "Default")
      (node (ref "RL143") (pin "6") (pintype "passive"))
    )
    (net (code "271") (name "unconnected-(RL144-Pad4)") (class "Default")
      (node (ref "RL144") (pin "4") (pintype "passive"))
    )
    (net (code "272") (name "unconnected-(RL144-Pad5)") (class "Default")
      (node (ref "RL144") (pin "5") (pintype "passive"))
    )
    (net (code "273") (name "unconnected-(RL144-Pad6)") (class "Default")
      (node (ref "RL144") (pin "6") (pintype "passive"))
    )
  )
)
